# FDCAN.net
KiCad netlist of a schematic drawn in Altium Designer
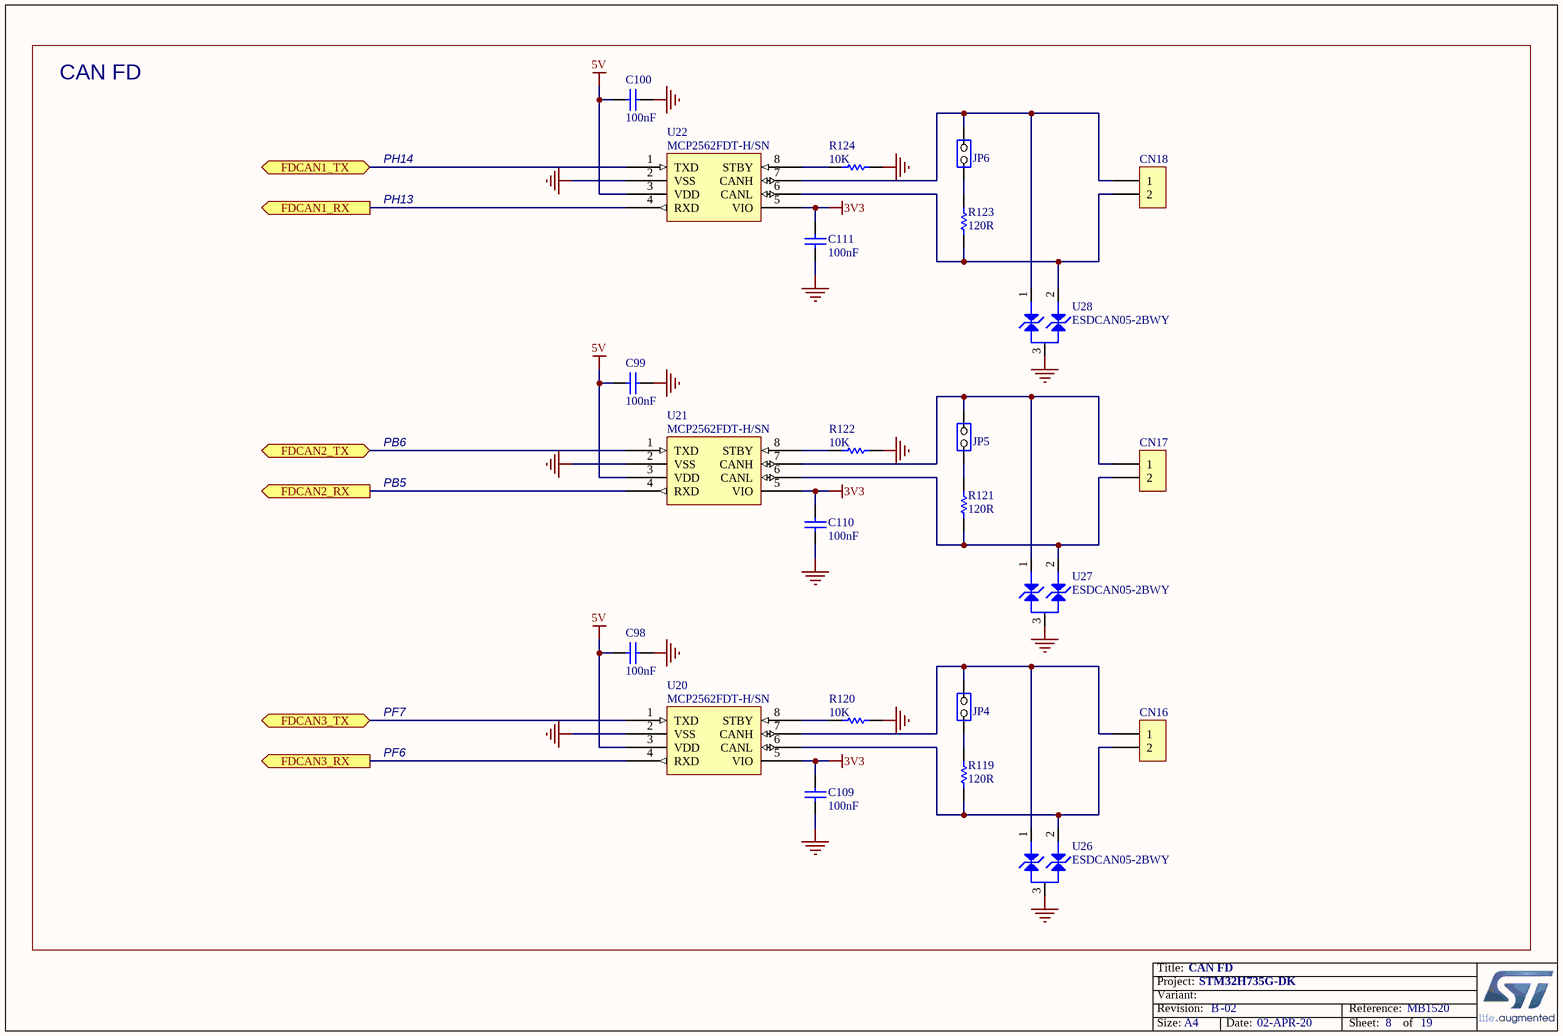
[diagram p0: FDCAN.SchDoc]

(export (version "E")
  (design (tool "Eeschema 10.0.6"))
  (components
    (comp (ref "C98")
      (value "100nF")
      (footprint "C0402")
      (description "Capacitor, MLCC, 100nF, 16V, X7R, 10%, 0402, T=0,5mm")
      (fields
        (field (name "INTERNAL_PART_NUMBER") "MCD-00102")
        (field (name "MANUFACTURER_PART_NUMBER") "CC0402KRX7R7BB104")
        (field (name "PROVIDED_BY") "SUBCO")
      )
      (libsource (lib "MCD_PARTS_database") (part "Capacitor"))
    )
    (comp (ref "C99")
      (value "100nF")
      (footprint "C0402")
      (description "Capacitor, MLCC, 100nF, 16V, X7R, 10%, 0402, T=0,5mm")
      (fields
        (field (name "INTERNAL_PART_NUMBER") "MCD-00102")
        (field (name "MANUFACTURER_PART_NUMBER") "CC0402KRX7R7BB104")
        (field (name "PROVIDED_BY") "SUBCO")
      )
      (libsource (lib "MCD_PARTS_database") (part "Capacitor"))
    )
    (comp (ref "C100")
      (value "100nF")
      (footprint "C0402")
      (description "Capacitor, MLCC, 100nF, 16V, X7R, 10%, 0402, T=0,5mm")
      (fields
        (field (name "INTERNAL_PART_NUMBER") "MCD-00102")
        (field (name "MANUFACTURER_PART_NUMBER") "CC0402KRX7R7BB104")
        (field (name "PROVIDED_BY") "SUBCO")
      )
      (libsource (lib "MCD_PARTS_database") (part "Capacitor"))
    )
    (comp (ref "C109")
      (value "100nF")
      (footprint "C0402")
      (description "Capacitor, MLCC, 100nF, 16V, X7R, 10%, 0402, T=0,5mm")
      (fields
        (field (name "INTERNAL_PART_NUMBER") "MCD-00102")
        (field (name "MANUFACTURER_PART_NUMBER") "CC0402KRX7R7BB104")
        (field (name "PROVIDED_BY") "SUBCO")
      )
      (libsource (lib "MCD_PARTS_database") (part "Capacitor"))
    )
    (comp (ref "C110")
      (value "100nF")
      (footprint "C0402")
      (description "Capacitor, MLCC, 100nF, 16V, X7R, 10%, 0402, T=0,5mm")
      (fields
        (field (name "INTERNAL_PART_NUMBER") "MCD-00102")
        (field (name "MANUFACTURER_PART_NUMBER") "CC0402KRX7R7BB104")
        (field (name "PROVIDED_BY") "SUBCO")
      )
      (libsource (lib "MCD_PARTS_database") (part "Capacitor"))
    )
    (comp (ref "C111")
      (value "100nF")
      (footprint "C0402")
      (description "Capacitor, MLCC, 100nF, 16V, X7R, 10%, 0402, T=0,5mm")
      (fields
        (field (name "INTERNAL_PART_NUMBER") "MCD-00102")
        (field (name "MANUFACTURER_PART_NUMBER") "CC0402KRX7R7BB104")
        (field (name "PROVIDED_BY") "SUBCO")
      )
      (libsource (lib "MCD_PARTS_database") (part "Capacitor"))
    )
    (comp (ref "CN16")
      (value "Header 2x1")
      (footprint "CON_988-JIUBABA_PHFS25-11-02-G0B115-T-1")
      (description "Header, 2x1, 2.54mm, VR, TH, Height 6mm/3mm")
      (fields
        (field (name "INTERNAL_PART_NUMBER") "MCD-00314")
        (field (name "MANUFACTURER_PART_NUMBER") "PHFS25-11-02-G0B115-T-1")
        (field (name "PROVIDED_BY") "SUBCO")
      )
      (libsource (lib "MCD_PARTS_database") (part "Header 2x1"))
    )
    (comp (ref "CN17")
      (value "Header 2x1")
      (footprint "CON_988-JIUBABA_PHFS25-11-02-G0B115-T-1")
      (description "Header, 2x1, 2.54mm, VR, TH, Height 6mm/3mm")
      (fields
        (field (name "INTERNAL_PART_NUMBER") "MCD-00314")
        (field (name "MANUFACTURER_PART_NUMBER") "PHFS25-11-02-G0B115-T-1")
        (field (name "PROVIDED_BY") "SUBCO")
      )
      (libsource (lib "MCD_PARTS_database") (part "Header 2x1"))
    )
    (comp (ref "CN18")
      (value "Header 2x1")
      (footprint "CON_988-JIUBABA_PHFS25-11-02-G0B115-T-1")
      (description "Header, 2x1, 2.54mm, VR, TH, Height 6mm/3mm")
      (fields
        (field (name "INTERNAL_PART_NUMBER") "MCD-00314")
        (field (name "MANUFACTURER_PART_NUMBER") "PHFS25-11-02-G0B115-T-1")
        (field (name "PROVIDED_BY") "SUBCO")
      )
      (libsource (lib "MCD_PARTS_database") (part "Header 2x1"))
    )
    (comp (ref "JP4")
      (value "Jumper_Header 2x1")
      (footprint "CON_SAMTEC_TSW-102-07-G-S")
      (description "Header, 2x1, 2,54mm, VR, TH, Height 5.84mm/2.54mm")
      (fields
        (field (name "INTERNAL_PART_NUMBER") "MCD-00045")
        (field (name "MANUFACTURER_PART_NUMBER") "TSW-102-07-x-S")
        (field (name "PROVIDED_BY") "SUBCO")
      )
      (libsource (lib "MCD_PARTS_database") (part "Jumper_Header 2x1"))
    )
    (comp (ref "JP5")
      (value "Jumper_Header 2x1")
      (footprint "CON_SAMTEC_TSW-102-07-G-S")
      (description "Header, 2x1, 2,54mm, VR, TH, Height 5.84mm/2.54mm")
      (fields
        (field (name "INTERNAL_PART_NUMBER") "MCD-00045")
        (field (name "MANUFACTURER_PART_NUMBER") "TSW-102-07-x-S")
        (field (name "PROVIDED_BY") "SUBCO")
      )
      (libsource (lib "MCD_PARTS_database") (part "Jumper_Header 2x1"))
    )
    (comp (ref "JP6")
      (value "Jumper_Header 2x1")
      (footprint "CON_SAMTEC_TSW-102-07-G-S")
      (description "Header, 2x1, 2,54mm, VR, TH, Height 5.84mm/2.54mm")
      (fields
        (field (name "INTERNAL_PART_NUMBER") "MCD-00045")
        (field (name "MANUFACTURER_PART_NUMBER") "TSW-102-07-x-S")
        (field (name "PROVIDED_BY") "SUBCO")
      )
      (libsource (lib "MCD_PARTS_database") (part "Jumper_Header 2x1"))
    )
    (comp (ref "R119")
      (value "120R")
      (footprint "R0402")
      (description "Resistor,120R,0402,1%,1/16W")
      (fields
        (field (name "INTERNAL_PART_NUMBER") "MCD-00194")
        (field (name "MANUFACTURER_PART_NUMBER") "RC0402FR-07120RL")
        (field (name "PROVIDED_BY") "SUBCO")
      )
      (libsource (lib "MCD_PARTS_database") (part "Resistor"))
    )
    (comp (ref "R120")
      (value "10K")
      (footprint "R0402")
      (description "Resistor,10K,0402,1%,1/16W")
      (fields
        (field (name "INTERNAL_PART_NUMBER") "MCD-00053")
        (field (name "MANUFACTURER_PART_NUMBER") "RC0402FR-0710KL")
        (field (name "PROVIDED_BY") "SUBCO")
      )
      (libsource (lib "MCD_PARTS_database") (part "Resistor"))
    )
    (comp (ref "R121")
      (value "120R")
      (footprint "R0402")
      (description "Resistor,120R,0402,1%,1/16W")
      (fields
        (field (name "INTERNAL_PART_NUMBER") "MCD-00194")
        (field (name "MANUFACTURER_PART_NUMBER") "RC0402FR-07120RL")
        (field (name "PROVIDED_BY") "SUBCO")
      )
      (libsource (lib "MCD_PARTS_database") (part "Resistor"))
    )
    (comp (ref "R122")
      (value "10K")
      (footprint "R0402")
      (description "Resistor,10K,0402,1%,1/16W")
      (fields
        (field (name "INTERNAL_PART_NUMBER") "MCD-00053")
        (field (name "MANUFACTURER_PART_NUMBER") "RC0402FR-0710KL")
        (field (name "PROVIDED_BY") "SUBCO")
      )
      (libsource (lib "MCD_PARTS_database") (part "Resistor"))
    )
    (comp (ref "R123")
      (value "120R")
      (footprint "R0402")
      (description "Resistor,120R,0402,1%,1/16W")
      (fields
        (field (name "INTERNAL_PART_NUMBER") "MCD-00194")
        (field (name "MANUFACTURER_PART_NUMBER") "RC0402FR-07120RL")
        (field (name "PROVIDED_BY") "SUBCO")
      )
      (libsource (lib "MCD_PARTS_database") (part "Resistor"))
    )
    (comp (ref "R124")
      (value "10K")
      (footprint "R0402")
      (description "Resistor,10K,0402,1%,1/16W")
      (fields
        (field (name "INTERNAL_PART_NUMBER") "MCD-00053")
        (field (name "MANUFACTURER_PART_NUMBER") "RC0402FR-0710KL")
        (field (name "PROVIDED_BY") "SUBCO")
      )
      (libsource (lib "MCD_PARTS_database") (part "Resistor"))
    )
    (comp (ref "U20")
      (value "MCP2562FDT-H/SN")
      (footprint "ICC_SO8_5X4_P127")
      (description "High-Speed CAN Flexible Data Rate Transceiver")
      (fields
        (field (name "INTERNAL_PART_NUMBER") "MCD-00129")
        (field (name "MANUFACTURER") "MICROCHIP")
        (field (name "PROVIDED_BY") "SUBCO")
      )
      (libsource (lib "MCD_PARTS_database") (part "MCP2562FD"))
    )
    (comp (ref "U21")
      (value "MCP2562FDT-H/SN")
      (footprint "ICC_SO8_5X4_P127")
      (description "High-Speed CAN Flexible Data Rate Transceiver")
      (fields
        (field (name "INTERNAL_PART_NUMBER") "MCD-00129")
        (field (name "MANUFACTURER") "MICROCHIP")
        (field (name "PROVIDED_BY") "SUBCO")
      )
      (libsource (lib "MCD_PARTS_database") (part "MCP2562FD"))
    )
    (comp (ref "U22")
      (value "MCP2562FDT-H/SN")
      (footprint "ICC_SO8_5X4_P127")
      (description "High-Speed CAN Flexible Data Rate Transceiver")
      (fields
        (field (name "INTERNAL_PART_NUMBER") "MCD-00129")
        (field (name "MANUFACTURER") "MICROCHIP")
        (field (name "PROVIDED_BY") "SUBCO")
      )
      (libsource (lib "MCD_PARTS_database") (part "MCP2562FD"))
    )
    (comp (ref "U26")
      (value "ESDCAN05-2BWY")
      (footprint "DIO_SOT323")
      (fields
        (field (name "INTERNAL_PART_NUMBER") "MCD-01358")
        (field (name "MANUFACTURER") "STMICROELECTRONICS")
        (field (name "BMS_PART_NUMBER") "9179021")
        (field (name "PROVIDED_BY") "SUBCO with ST control")
      )
      (libsource (lib "MCD_PARTS_database") (part "ESD-TRANSIL-DUAL-BIDIR"))
    )
    (comp (ref "U27")
      (value "ESDCAN05-2BWY")
      (footprint "DIO_SOT323")
      (fields
        (field (name "INTERNAL_PART_NUMBER") "MCD-01358")
        (field (name "MANUFACTURER") "STMICROELECTRONICS")
        (field (name "BMS_PART_NUMBER") "9179021")
        (field (name "PROVIDED_BY") "SUBCO with ST control")
      )
      (libsource (lib "MCD_PARTS_database") (part "ESD-TRANSIL-DUAL-BIDIR"))
    )
    (comp (ref "U28")
      (value "ESDCAN05-2BWY")
      (footprint "DIO_SOT323")
      (fields
        (field (name "INTERNAL_PART_NUMBER") "MCD-01358")
        (field (name "MANUFACTURER") "STMICROELECTRONICS")
        (field (name "BMS_PART_NUMBER") "9179021")
        (field (name "PROVIDED_BY") "SUBCO with ST control")
      )
      (libsource (lib "MCD_PARTS_database") (part "ESD-TRANSIL-DUAL-BIDIR"))
    )
  )
  (nets
    (net (code "1") (name "/FDCAN1_RX") (class "Default")
      (node (ref "U22") (pin "4") (pinfunction "RXD_4") (pintype "output"))
    )
    (net (code "2") (name "/FDCAN1_TX") (class "Default")
      (node (ref "U22") (pin "1") (pinfunction "TXD_1") (pintype "input"))
    )
    (net (code "3") (name "/FDCAN2_RX") (class "Default")
      (node (ref "U21") (pin "4") (pinfunction "RXD_4") (pintype "output"))
    )
    (net (code "4") (name "/FDCAN2_TX") (class "Default")
      (node (ref "U21") (pin "1") (pinfunction "TXD_1") (pintype "input"))
    )
    (net (code "5") (name "/FDCAN3_RX") (class "Default")
      (node (ref "U20") (pin "4") (pinfunction "RXD_4") (pintype "output"))
    )
    (net (code "6") (name "/FDCAN3_TX") (class "Default")
      (node (ref "U20") (pin "1") (pinfunction "TXD_1") (pintype "input"))
    )
    (net (code "7") (name "3V3") (class "Default")
      (node (ref "C109") (pin "2") (pinfunction "2_2") (pintype "passive"))
      (node (ref "C110") (pin "2") (pinfunction "2_2") (pintype "passive"))
      (node (ref "C111") (pin "2") (pinfunction "2_2") (pintype "passive"))
      (node (ref "U20") (pin "5") (pinfunction "VIO_5") (pintype "power_in"))
      (node (ref "U21") (pin "5") (pinfunction "VIO_5") (pintype "power_in"))
      (node (ref "U22") (pin "5") (pinfunction "VIO_5") (pintype "power_in"))
    )
    (net (code "8") (name "5V") (class "Default")
      (node (ref "C100") (pin "2") (pinfunction "2_2") (pintype "passive"))
      (node (ref "C98") (pin "2") (pinfunction "2_2") (pintype "passive"))
      (node (ref "C99") (pin "2") (pinfunction "2_2") (pintype "passive"))
      (node (ref "U20") (pin "3") (pinfunction "VDD_3") (pintype "power_in"))
      (node (ref "U21") (pin "3") (pinfunction "VDD_3") (pintype "power_in"))
      (node (ref "U22") (pin "3") (pinfunction "VDD_3") (pintype "power_in"))
    )
    (net (code "9") (name "GND") (class "Default")
      (node (ref "C100") (pin "1") (pinfunction "1_1") (pintype "passive"))
      (node (ref "C109") (pin "1") (pinfunction "1_1") (pintype "passive"))
      (node (ref "C110") (pin "1") (pinfunction "1_1") (pintype "passive"))
      (node (ref "C111") (pin "1") (pinfunction "1_1") (pintype "passive"))
      (node (ref "C98") (pin "1") (pinfunction "1_1") (pintype "passive"))
      (node (ref "C99") (pin "1") (pinfunction "1_1") (pintype "passive"))
      (node (ref "R120") (pin "2") (pinfunction "2_2") (pintype "passive"))
      (node (ref "R122") (pin "2") (pinfunction "2_2") (pintype "passive"))
      (node (ref "R124") (pin "2") (pinfunction "2_2") (pintype "passive"))
      (node (ref "U20") (pin "2") (pinfunction "VSS_2") (pintype "power_in"))
      (node (ref "U21") (pin "2") (pinfunction "VSS_2") (pintype "power_in"))
      (node (ref "U22") (pin "2") (pinfunction "VSS_2") (pintype "power_in"))
      (node (ref "U26") (pin "3") (pintype "passive"))
      (node (ref "U27") (pin "3") (pintype "passive"))
      (node (ref "U28") (pin "3") (pintype "passive"))
    )
    (net (code "10") (name "Net-(JP4-COMMON)") (class "Default")
      (node (ref "JP4") (pin "1") (pinfunction "COMMON_1") (pintype "passive"))
      (node (ref "R119") (pin "2") (pinfunction "2_2") (pintype "passive"))
    )
    (net (code "11") (name "Net-(JP4-NO)") (class "Default")
      (node (ref "CN16") (pin "1") (pinfunction "1_1") (pintype "passive"))
      (node (ref "JP4") (pin "2") (pinfunction "NO_2") (pintype "passive"))
      (node (ref "U20") (pin "7") (pinfunction "CANH_7") (pintype "bidirectional"))
      (node (ref "U26") (pin "1") (pintype "passive"))
    )
    (net (code "12") (name "Net-(JP5-COMMON)") (class "Default")
      (node (ref "JP5") (pin "1") (pinfunction "COMMON_1") (pintype "passive"))
      (node (ref "R121") (pin "2") (pinfunction "2_2") (pintype "passive"))
    )
    (net (code "13") (name "Net-(JP5-NO)") (class "Default")
      (node (ref "CN17") (pin "1") (pinfunction "1_1") (pintype "passive"))
      (node (ref "JP5") (pin "2") (pinfunction "NO_2") (pintype "passive"))
      (node (ref "U21") (pin "7") (pinfunction "CANH_7") (pintype "bidirectional"))
      (node (ref "U27") (pin "1") (pintype "passive"))
    )
    (net (code "14") (name "Net-(JP6-COMMON)") (class "Default")
      (node (ref "JP6") (pin "1") (pinfunction "COMMON_1") (pintype "passive"))
      (node (ref "R123") (pin "2") (pinfunction "2_2") (pintype "passive"))
    )
    (net (code "15") (name "Net-(JP6-NO)") (class "Default")
      (node (ref "CN18") (pin "1") (pinfunction "1_1") (pintype "passive"))
      (node (ref "JP6") (pin "2") (pinfunction "NO_2") (pintype "passive"))
      (node (ref "U22") (pin "7") (pinfunction "CANH_7") (pintype "bidirectional"))
      (node (ref "U28") (pin "1") (pintype "passive"))
    )
    (net (code "16") (name "Net-(U20-CANL)") (class "Default")
      (node (ref "CN16") (pin "2") (pinfunction "2_2") (pintype "passive"))
      (node (ref "R119") (pin "1") (pinfunction "1_1") (pintype "passive"))
      (node (ref "U20") (pin "6") (pinfunction "CANL_6") (pintype "bidirectional"))
      (node (ref "U26") (pin "2") (pintype "passive"))
    )
    (net (code "17") (name "Net-(U20-STBY)") (class "Default")
      (node (ref "R120") (pin "1") (pinfunction "1_1") (pintype "passive"))
      (node (ref "U20") (pin "8") (pinfunction "STBY_8") (pintype "input"))
    )
    (net (code "18") (name "Net-(U21-CANL)") (class "Default")
      (node (ref "CN17") (pin "2") (pinfunction "2_2") (pintype "passive"))
      (node (ref "R121") (pin "1") (pinfunction "1_1") (pintype "passive"))
      (node (ref "U21") (pin "6") (pinfunction "CANL_6") (pintype "bidirectional"))
      (node (ref "U27") (pin "2") (pintype "passive"))
    )
    (net (code "19") (name "Net-(U21-STBY)") (class "Default")
      (node (ref "R122") (pin "1") (pinfunction "1_1") (pintype "passive"))
      (node (ref "U21") (pin "8") (pinfunction "STBY_8") (pintype "input"))
    )
    (net (code "20") (name "Net-(U22-CANL)") (class "Default")
      (node (ref "CN18") (pin "2") (pinfunction "2_2") (pintype "passive"))
      (node (ref "R123") (pin "1") (pinfunction "1_1") (pintype "passive"))
      (node (ref "U22") (pin "6") (pinfunction "CANL_6") (pintype "bidirectional"))
      (node (ref "U28") (pin "2") (pintype "passive"))
    )
    (net (code "21") (name "Net-(U22-STBY)") (class "Default")
      (node (ref "R124") (pin "1") (pinfunction "1_1") (pintype "passive"))
      (node (ref "U22") (pin "8") (pinfunction "STBY_8") (pintype "input"))
    )
  )
)
